# GainBlock.net
KiCad netlist of a schematic drawn in Altium Designer
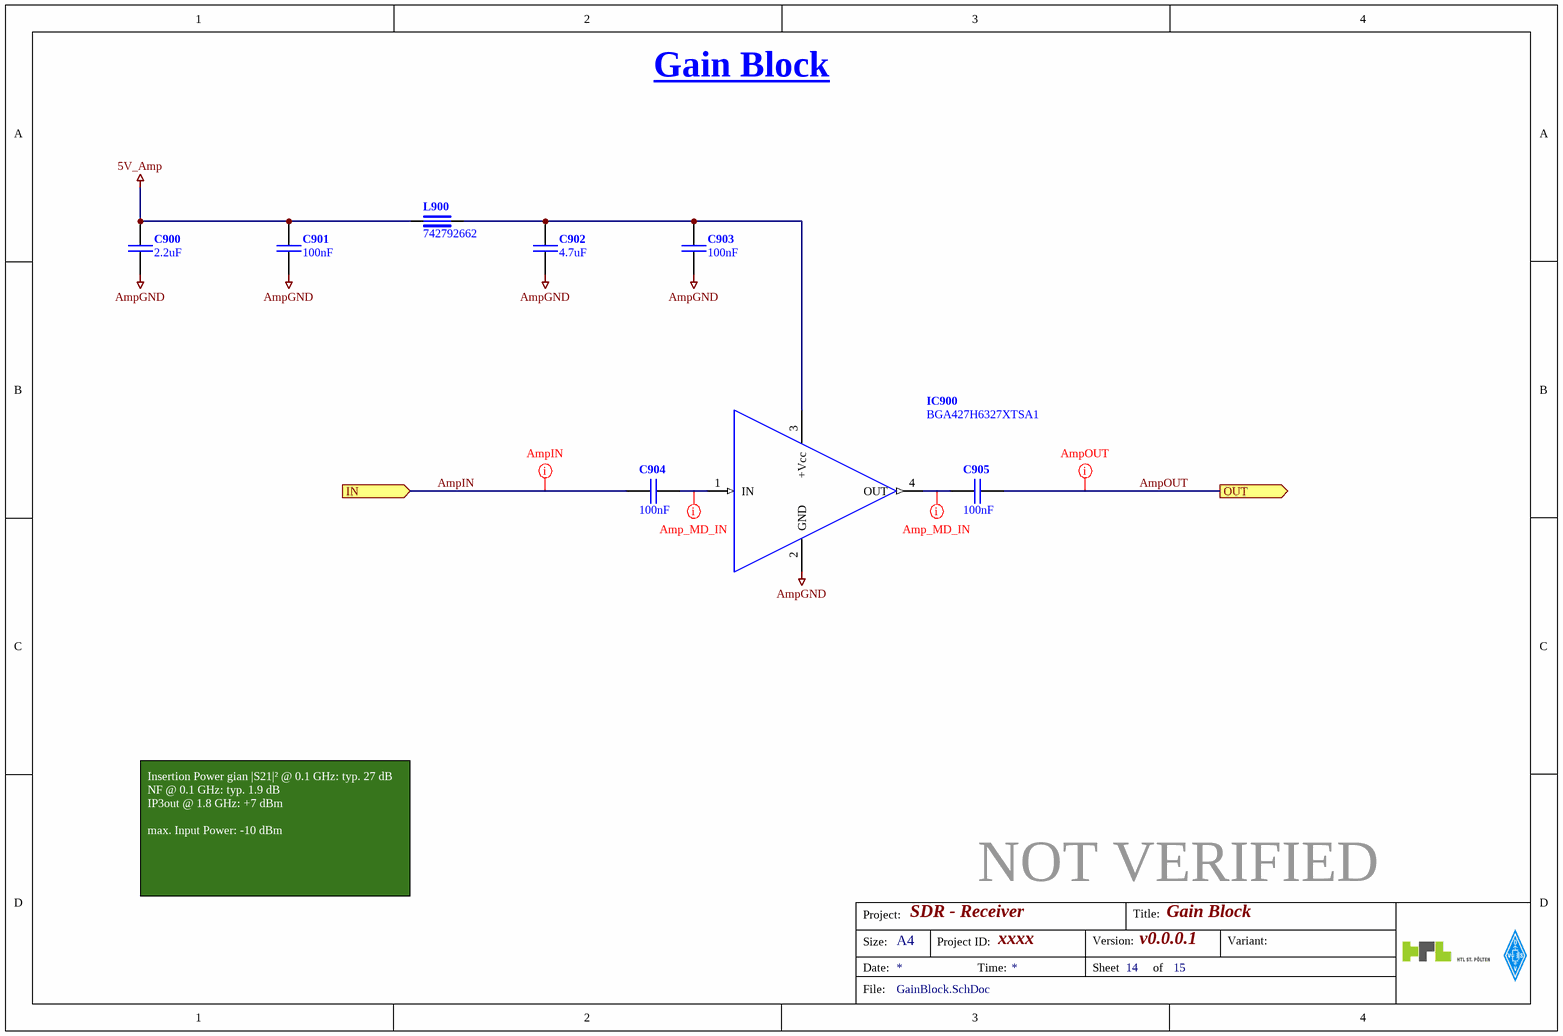
[diagram p0: GainBlock.SchDoc]

(export (version "E")
  (design (tool "Eeschema 10.0.6"))
  (components
    (comp (ref "C900")
      (value "2.2uF")
      (footprint "PrometheusLib:C_0805_N [CAPC2013N IPC]")
      (libsource (lib "PrometheusLib") (part "C_GENERIC"))
    )
    (comp (ref "C901")
      (value "100nF")
      (footprint "PrometheusLib:C_0603_N [CAPC1608N IPC]")
      (libsource (lib "PrometheusLib") (part "C_GENERIC"))
    )
    (comp (ref "C902")
      (value "4.7uF")
      (footprint "PrometheusLib:C_0805_N [CAPC2013N IPC]")
      (libsource (lib "PrometheusLib") (part "C_GENERIC"))
    )
    (comp (ref "C903")
      (value "100nF")
      (footprint "PrometheusLib:C_0603_N [CAPC1608N IPC]")
      (libsource (lib "PrometheusLib") (part "C_GENERIC"))
    )
    (comp (ref "C904")
      (value "100nF")
      (footprint "PrometheusLib:C_0603_N [CAPC1608N IPC]")
      (fields (field (name "PROMETHEUS_MANPARTNO") "06031U101FAT2A"))
      (libsource (lib "PrometheusLib") (part "C_GENERIC"))
    )
    (comp (ref "C905")
      (value "100nF")
      (footprint "PrometheusLib:C_0603_N [CAPC1608N IPC]")
      (fields (field (name "PROMETHEUS_MANPARTNO") "06031U101FAT2A"))
      (libsource (lib "PrometheusLib") (part "C_GENERIC"))
    )
    (comp (ref "IC900")
      (value "BGA427H6327XTSA1")
      (footprint "SOT130P210X100-4N IPC")
      (libsource (lib "PrometheusLib") (part "IC_BGA427"))
    )
    (comp (ref "L900")
      (value "742792662")
      (footprint "PrometheusLib:L_0603_N [INDC1608N IPC]")
      (libsource (lib "PrometheusLib") (part "FB_GENERIC"))
    )
  )
  (nets
    (net (code "1") (name "/AmpIN") (class "Default") (node (ref "C904") (pin "2") (pintype "passive")))
    (net (code "2") (name "/AmpOUT") (class "Default") (node (ref "C905") (pin "1") (pintype "passive")))
    (net (code "3") (name "5V_Amp") (class "Default")
      (node (ref "C900") (pin "1") (pintype "passive"))
      (node (ref "C901") (pin "1") (pintype "passive"))
      (node (ref "L900") (pin "2") (pintype "passive"))
    )
    (net (code "4") (name "AmpGND") (class "Default")
      (node (ref "C900") (pin "2") (pintype "passive"))
      (node (ref "C901") (pin "2") (pintype "passive"))
      (node (ref "C902") (pin "2") (pintype "passive"))
      (node (ref "C903") (pin "2") (pintype "passive"))
      (node (ref "IC900") (pin "2") (pinfunction "GND_2") (pintype "passive"))
    )
    (net (code "5") (name "Net-(IC900-+Vcc)") (class "Default")
      (node (ref "C902") (pin "1") (pintype "passive"))
      (node (ref "C903") (pin "1") (pintype "passive"))
      (node (ref "IC900") (pin "3") (pinfunction "+Vcc_3") (pintype "passive"))
      (node (ref "L900") (pin "1") (pintype "passive"))
    )
    (net (code "6") (name "Net-(IC900-IN)") (class "Default")
      (node (ref "C904") (pin "1") (pintype "passive"))
      (node (ref "IC900") (pin "1") (pinfunction "IN_1") (pintype "input"))
    )
    (net (code "7") (name "Net-(IC900-OUT)") (class "Default")
      (node (ref "C905") (pin "2") (pintype "passive"))
      (node (ref "IC900") (pin "4") (pinfunction "OUT_4") (pintype "output"))
    )
  )
)
